# PERIPHERAL.net
KiCad netlist of a schematic drawn in Altium Designer
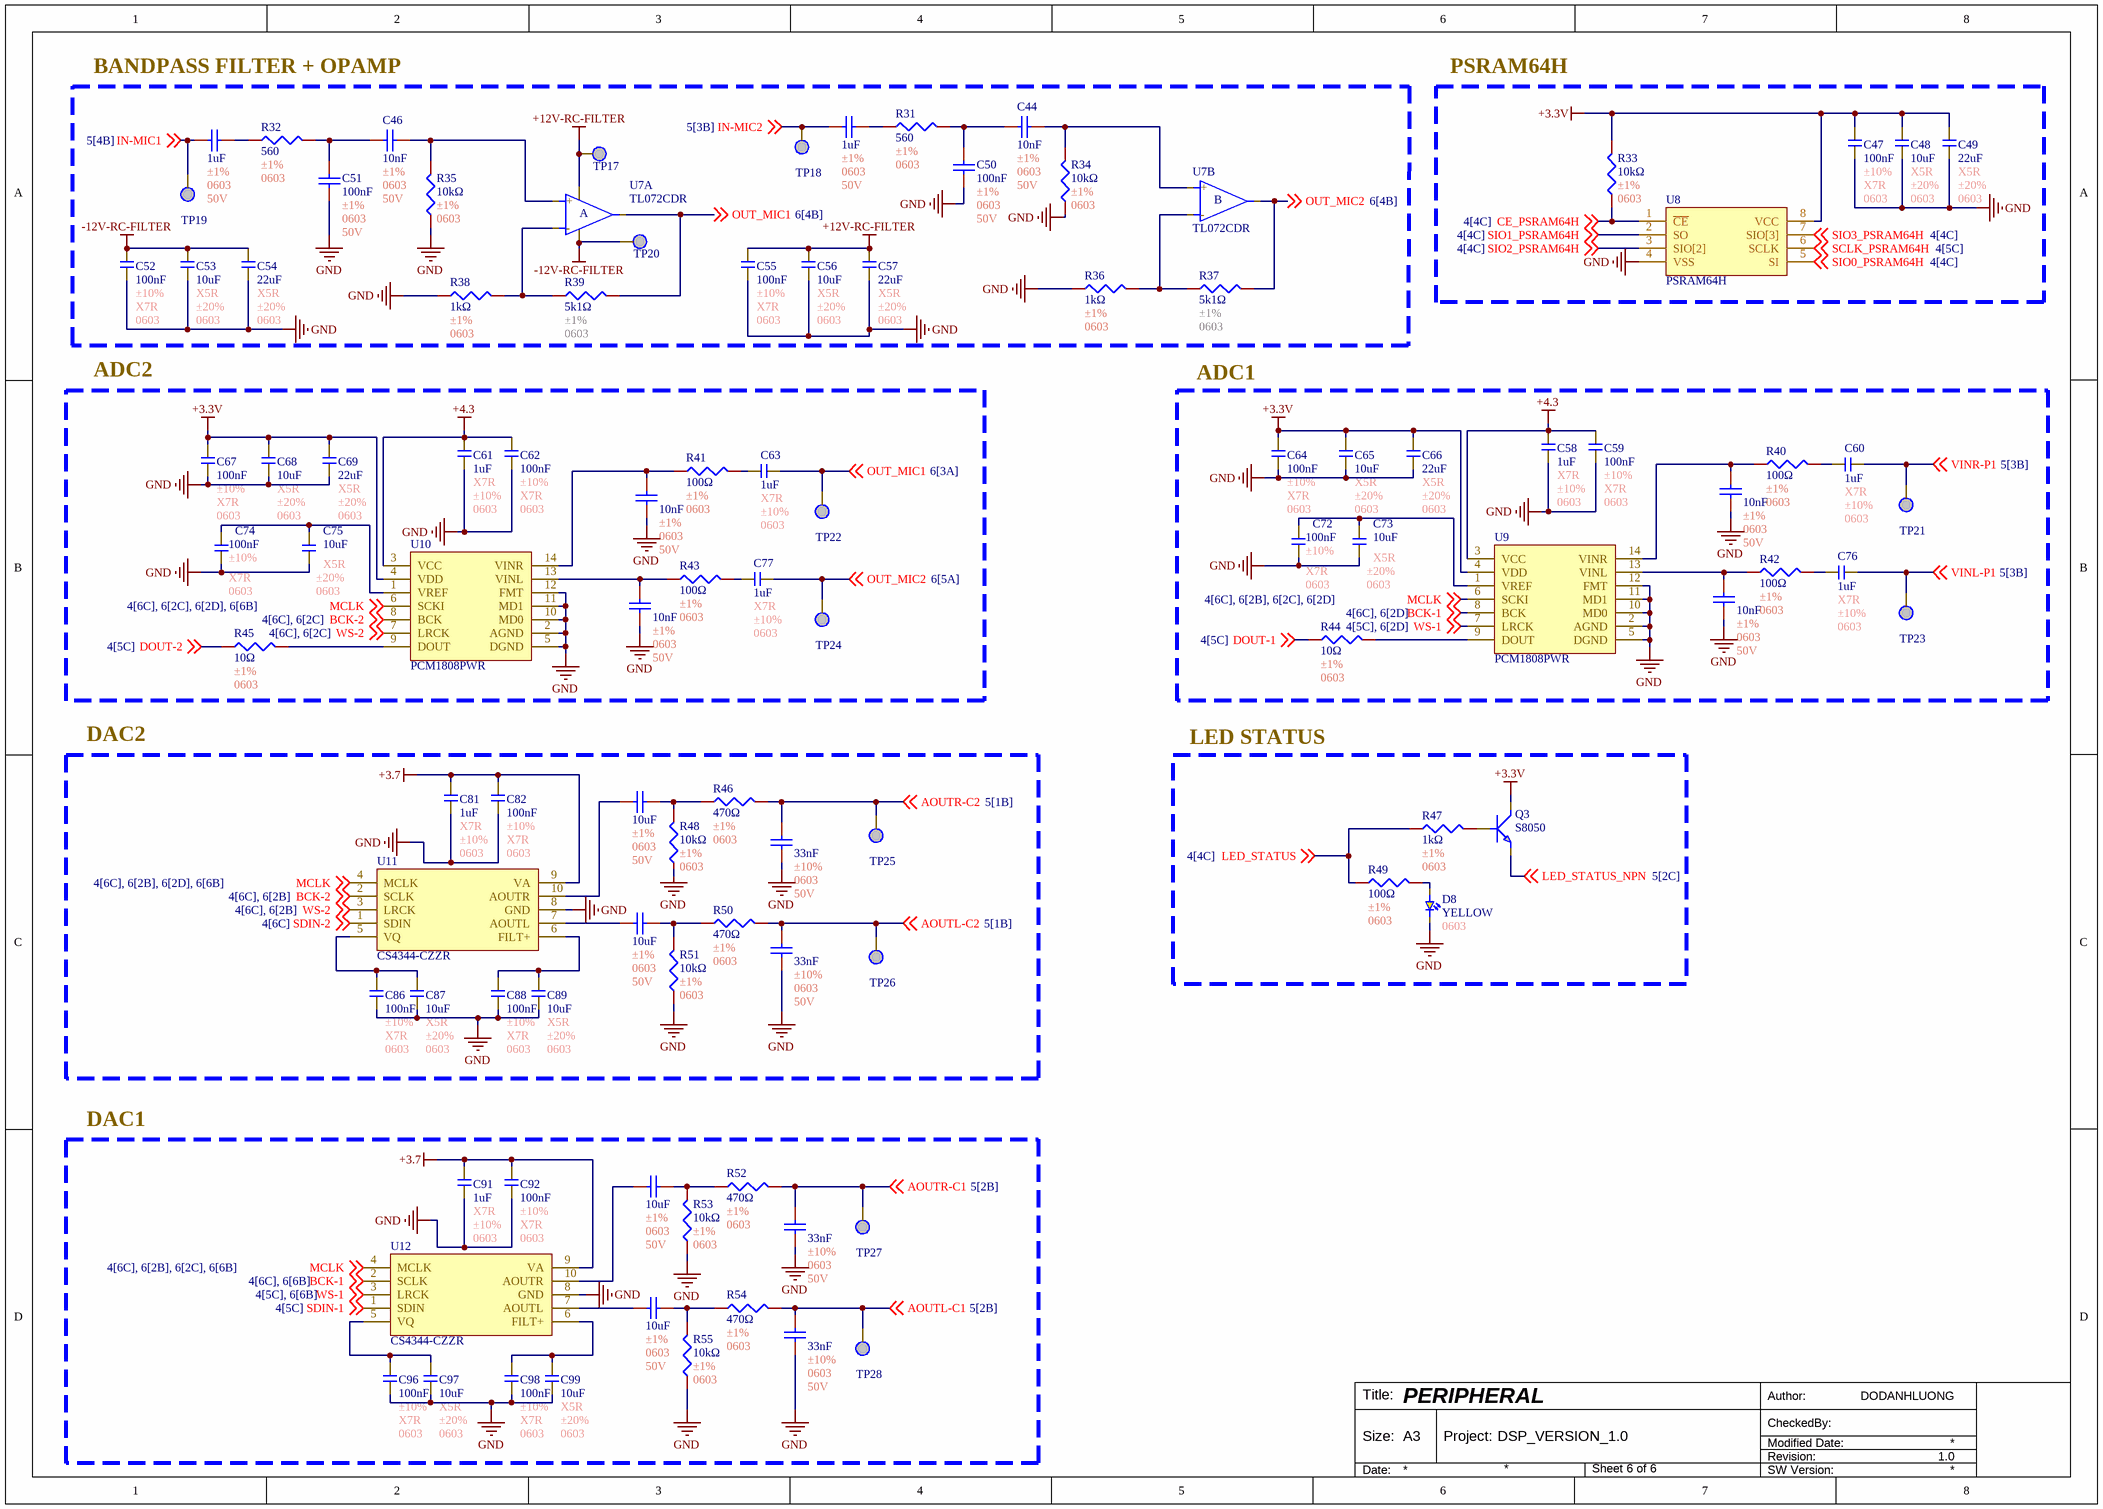
[diagram p0: PERIPHERAL.SchDoc]

(export (version "E")
  (design (tool "Eeschema 10.0.6"))
  (components
    (comp (ref "C43")
      (value "1uF")
      (footprint "C0603")
      (description "50V 10pF NP0 ±1% 0402 Multilayer Ceramic Capacitors MLCC - SMD/SMT ROHS")
      (fields
        (field (name "MANUFACTURER") "YAGEO")
        (field (name "MFR. PART #") "CC0402FRNPO9BN100")
        (field (name "TOLERANCE") "±1%")
        (field (name "PACKAGE") "0603")
        (field (name "VOLTAGE RATING") "50V")
      )
      (libsource (lib "Capital") (part "C0603_1uF_±1%"))
    )
    (comp (ref "C44")
      (value "10nF")
      (footprint "C0603")
      (description "50V 10pF NP0 ±1% 0402 Multilayer Ceramic Capacitors MLCC - SMD/SMT ROHS")
      (fields
        (field (name "MANUFACTURER") "YAGEO")
        (field (name "MFR. PART #") "CC0402FRNPO9BN100")
        (field (name "TOLERANCE") "±1%")
        (field (name "PACKAGE") "0603")
        (field (name "VOLTAGE RATING") "50V")
      )
      (libsource (lib "Capital") (part "C0603_10nF_±1%"))
    )
    (comp (ref "C45")
      (value "1uF")
      (footprint "C0603")
      (description "50V 10pF NP0 ±1% 0402 Multilayer Ceramic Capacitors MLCC - SMD/SMT ROHS")
      (fields
        (field (name "MANUFACTURER") "YAGEO")
        (field (name "MFR. PART #") "CC0402FRNPO9BN100")
        (field (name "TOLERANCE") "±1%")
        (field (name "PACKAGE") "0603")
        (field (name "VOLTAGE RATING") "50V")
      )
      (libsource (lib "Capital") (part "C0603_1uF_±1%"))
    )
    (comp (ref "C46")
      (value "10nF")
      (footprint "C0603")
      (description "50V 10pF NP0 ±1% 0402 Multilayer Ceramic Capacitors MLCC - SMD/SMT ROHS")
      (fields
        (field (name "MANUFACTURER") "YAGEO")
        (field (name "MFR. PART #") "CC0402FRNPO9BN100")
        (field (name "TOLERANCE") "±1%")
        (field (name "PACKAGE") "0603")
        (field (name "VOLTAGE RATING") "50V")
      )
      (libsource (lib "Capital") (part "C0603_10nF_±1%"))
    )
    (comp (ref "C47")
      (value "100nF")
      (footprint "C0603")
      (description "50V 100nF X7R ±10% 0603 Multilayer Ceramic Capacitors MLCC - SMD/SMT ROHS")
      (fields
        (field (name "MANUFACTURER") "YAGEO")
        (field (name "MFR. PART #") "CC0603KRX7R9BB104")
        (field (name "TOLERANCE") "±10%")
        (field (name "TEMPERATURE COEFFICIENT") "X7R")
        (field (name "PACKAGE") "0603")
      )
      (libsource (lib "DSP_VERSION_1.0") (part "C0603_100nF_±10%_X7R"))
    )
    (comp (ref "C48")
      (value "10uF")
      (footprint "C0603")
      (description "25V 10uF X5R ±20% 0603 Multilayer Ceramic Capacitors MLCC - SMD/SMT ROHS")
      (fields
        (field (name "MANUFACTURER") "YAGEO")
        (field (name "MFR. PART #") "CC0603MRX5R8BB106")
        (field (name "TEMPERATURE COEFFICIENT") "X5R")
        (field (name "TOLERANCE") "±20%")
        (field (name "PACKAGE") "0603")
      )
      (libsource (lib "DSP_VERSION_1.0") (part "C0603_10uF_±10%_X7R"))
    )
    (comp (ref "C49")
      (value "22uF")
      (footprint "C0603")
      (description "6.3V 22uF X5R ±20% 0603 Multilayer Ceramic Capacitors MLCC - SMD/SMT ROHS")
      (fields
        (field (name "MANUFACTURER") "YAGEO")
        (field (name "MFR. PART #") "CC0603MRX5R5BB226")
        (field (name "TEMPERATURE COEFFICIENT") "X5R")
        (field (name "TOLERANCE") "±20%")
        (field (name "PACKAGE") "0603")
      )
      (libsource (lib "DSP_VERSION_1.0") (part "C0603_22uF_±20%_X5R"))
    )
    (comp (ref "C50")
      (value "100nF")
      (footprint "C0603")
      (description "50V 10pF NP0 ±1% 0402 Multilayer Ceramic Capacitors MLCC - SMD/SMT ROHS")
      (fields
        (field (name "MANUFACTURER") "YAGEO")
        (field (name "MFR. PART #") "CC0402FRNPO9BN100")
        (field (name "TOLERANCE") "±1%")
        (field (name "PACKAGE") "0603")
        (field (name "VOLTAGE RATING") "50V")
      )
      (libsource (lib "Capital") (part "C0603_10nF_±1%"))
    )
    (comp (ref "C51")
      (value "100nF")
      (footprint "C0603")
      (description "50V 10pF NP0 ±1% 0402 Multilayer Ceramic Capacitors MLCC - SMD/SMT ROHS")
      (fields
        (field (name "MANUFACTURER") "YAGEO")
        (field (name "MFR. PART #") "CC0402FRNPO9BN100")
        (field (name "TOLERANCE") "±1%")
        (field (name "PACKAGE") "0603")
        (field (name "VOLTAGE RATING") "50V")
      )
      (libsource (lib "Capital") (part "C0603_10nF_±1%"))
    )
    (comp (ref "C52")
      (value "100nF")
      (footprint "C0603")
      (description "50V 100nF X7R ±10% 0603 Multilayer Ceramic Capacitors MLCC - SMD/SMT ROHS")
      (fields
        (field (name "MANUFACTURER") "YAGEO")
        (field (name "MFR. PART #") "CC0603KRX7R9BB104")
        (field (name "TOLERANCE") "±10%")
        (field (name "TEMPERATURE COEFFICIENT") "X7R")
        (field (name "PACKAGE") "0603")
      )
      (libsource (lib "DSP_VERSION_1.0") (part "C0603_100nF_±10%_X7R"))
    )
    (comp (ref "C53")
      (value "10uF")
      (footprint "C0603")
      (description "25V 10uF X5R ±20% 0603 Multilayer Ceramic Capacitors MLCC - SMD/SMT ROHS")
      (fields
        (field (name "MANUFACTURER") "YAGEO")
        (field (name "MFR. PART #") "CC0603MRX5R8BB106")
        (field (name "TEMPERATURE COEFFICIENT") "X5R")
        (field (name "TOLERANCE") "±20%")
        (field (name "PACKAGE") "0603")
      )
      (libsource (lib "DSP_VERSION_1.0") (part "C0603_10uF_±10%_X7R"))
    )
    (comp (ref "C54")
      (value "22uF")
      (footprint "C0603")
      (description "6.3V 22uF X5R ±20% 0603 Multilayer Ceramic Capacitors MLCC - SMD/SMT ROHS")
      (fields
        (field (name "MANUFACTURER") "YAGEO")
        (field (name "MFR. PART #") "CC0603MRX5R5BB226")
        (field (name "TEMPERATURE COEFFICIENT") "X5R")
        (field (name "TOLERANCE") "±20%")
        (field (name "PACKAGE") "0603")
      )
      (libsource (lib "DSP_VERSION_1.0") (part "C0603_22uF_±20%_X5R"))
    )
    (comp (ref "C55")
      (value "100nF")
      (footprint "C0603")
      (description "50V 100nF X7R ±10% 0603 Multilayer Ceramic Capacitors MLCC - SMD/SMT ROHS")
      (fields
        (field (name "MANUFACTURER") "YAGEO")
        (field (name "MFR. PART #") "CC0603KRX7R9BB104")
        (field (name "TOLERANCE") "±10%")
        (field (name "TEMPERATURE COEFFICIENT") "X7R")
        (field (name "PACKAGE") "0603")
      )
      (libsource (lib "DSP_VERSION_1.0") (part "C0603_100nF_±10%_X7R"))
    )
    (comp (ref "C56")
      (value "10uF")
      (footprint "C0603")
      (description "25V 10uF X5R ±20% 0603 Multilayer Ceramic Capacitors MLCC - SMD/SMT ROHS")
      (fields
        (field (name "MANUFACTURER") "YAGEO")
        (field (name "MFR. PART #") "CC0603MRX5R8BB106")
        (field (name "TEMPERATURE COEFFICIENT") "X5R")
        (field (name "TOLERANCE") "±20%")
        (field (name "PACKAGE") "0603")
      )
      (libsource (lib "DSP_VERSION_1.0") (part "C0603_10uF_±10%_X7R"))
    )
    (comp (ref "C57")
      (value "22uF")
      (footprint "C0603")
      (description "6.3V 22uF X5R ±20% 0603 Multilayer Ceramic Capacitors MLCC - SMD/SMT ROHS")
      (fields
        (field (name "MANUFACTURER") "YAGEO")
        (field (name "MFR. PART #") "CC0603MRX5R5BB226")
        (field (name "TEMPERATURE COEFFICIENT") "X5R")
        (field (name "TOLERANCE") "±20%")
        (field (name "PACKAGE") "0603")
      )
      (libsource (lib "DSP_VERSION_1.0") (part "C0603_22uF_±20%_X5R"))
    )
    (comp (ref "C58")
      (value "1uF")
      (footprint "C0603")
      (description "50V 1uF X7R ±10% 0603 Multilayer Ceramic Capacitors MLCC - SMD/SMT ROHS")
      (fields
        (field (name "MANUFACTURER") "YAGEO")
        (field (name "MFR. PART #") "CC0603KRX7R9BB105")
        (field (name "TEMPERATURE COEFFICIENT") "X7R")
        (field (name "TOLERANCE") "±10%")
        (field (name "PACKAGE") "0603")
      )
      (libsource (lib "DSP_VERSION_1.0") (part "C0603_1uF_±10%_X7R"))
    )
    (comp (ref "C59")
      (value "100nF")
      (footprint "C0603")
      (description "50V 100nF X7R ±10% 0603 Multilayer Ceramic Capacitors MLCC - SMD/SMT ROHS")
      (fields
        (field (name "MANUFACTURER") "YAGEO")
        (field (name "MFR. PART #") "CC0603KRX7R9BB104")
        (field (name "TOLERANCE") "±10%")
        (field (name "TEMPERATURE COEFFICIENT") "X7R")
        (field (name "PACKAGE") "0603")
      )
      (libsource (lib "DSP_VERSION_1.0") (part "C0603_100nF_±10%_X7R"))
    )
    (comp (ref "C60")
      (value "1uF")
      (footprint "C0603")
      (description "50V 1uF X7R ±10% 0603 Multilayer Ceramic Capacitors MLCC - SMD/SMT ROHS")
      (fields
        (field (name "MANUFACTURER") "YAGEO")
        (field (name "MFR. PART #") "CC0603KRX7R9BB105")
        (field (name "TEMPERATURE COEFFICIENT") "X7R")
        (field (name "TOLERANCE") "±10%")
        (field (name "PACKAGE") "0603")
      )
      (libsource (lib "DSP_VERSION_1.0") (part "C0603_1uF_±10%_X7R"))
    )
    (comp (ref "C61")
      (value "1uF")
      (footprint "C0603")
      (description "50V 1uF X7R ±10% 0603 Multilayer Ceramic Capacitors MLCC - SMD/SMT ROHS")
      (fields
        (field (name "MANUFACTURER") "YAGEO")
        (field (name "MFR. PART #") "CC0603KRX7R9BB105")
        (field (name "TEMPERATURE COEFFICIENT") "X7R")
        (field (name "TOLERANCE") "±10%")
        (field (name "PACKAGE") "0603")
      )
      (libsource (lib "DSP_VERSION_1.0") (part "C0603_1uF_±10%_X7R"))
    )
    (comp (ref "C62")
      (value "100nF")
      (footprint "C0603")
      (description "50V 100nF X7R ±10% 0603 Multilayer Ceramic Capacitors MLCC - SMD/SMT ROHS")
      (fields
        (field (name "MANUFACTURER") "YAGEO")
        (field (name "MFR. PART #") "CC0603KRX7R9BB104")
        (field (name "TOLERANCE") "±10%")
        (field (name "TEMPERATURE COEFFICIENT") "X7R")
        (field (name "PACKAGE") "0603")
      )
      (libsource (lib "DSP_VERSION_1.0") (part "C0603_100nF_±10%_X7R"))
    )
    (comp (ref "C63")
      (value "1uF")
      (footprint "C0603")
      (description "50V 1uF X7R ±10% 0603 Multilayer Ceramic Capacitors MLCC - SMD/SMT ROHS")
      (fields
        (field (name "MANUFACTURER") "YAGEO")
        (field (name "MFR. PART #") "CC0603KRX7R9BB105")
        (field (name "TEMPERATURE COEFFICIENT") "X7R")
        (field (name "TOLERANCE") "±10%")
        (field (name "PACKAGE") "0603")
      )
      (libsource (lib "DSP_VERSION_1.0") (part "C0603_1uF_±10%_X7R"))
    )
    (comp (ref "C64")
      (value "100nF")
      (footprint "C0603")
      (description "50V 100nF X7R ±10% 0603 Multilayer Ceramic Capacitors MLCC - SMD/SMT ROHS")
      (fields
        (field (name "MANUFACTURER") "YAGEO")
        (field (name "MFR. PART #") "CC0603KRX7R9BB104")
        (field (name "TOLERANCE") "±10%")
        (field (name "TEMPERATURE COEFFICIENT") "X7R")
        (field (name "PACKAGE") "0603")
      )
      (libsource (lib "DSP_VERSION_1.0") (part "C0603_100nF_±10%_X7R"))
    )
    (comp (ref "C65")
      (value "10uF")
      (footprint "C0603")
      (description "25V 10uF X5R ±20% 0603 Multilayer Ceramic Capacitors MLCC - SMD/SMT ROHS")
      (fields
        (field (name "MANUFACTURER") "YAGEO")
        (field (name "MFR. PART #") "CC0603MRX5R8BB106")
        (field (name "TEMPERATURE COEFFICIENT") "X5R")
        (field (name "TOLERANCE") "±20%")
        (field (name "PACKAGE") "0603")
      )
      (libsource (lib "DSP_VERSION_1.0") (part "C0603_10uF_±10%_X7R"))
    )
    (comp (ref "C66")
      (value "22uF")
      (footprint "C0603")
      (description "6.3V 22uF X5R ±20% 0603 Multilayer Ceramic Capacitors MLCC - SMD/SMT ROHS")
      (fields
        (field (name "MANUFACTURER") "YAGEO")
        (field (name "MFR. PART #") "CC0603MRX5R5BB226")
        (field (name "TEMPERATURE COEFFICIENT") "X5R")
        (field (name "TOLERANCE") "±20%")
        (field (name "PACKAGE") "0603")
      )
      (libsource (lib "DSP_VERSION_1.0") (part "C0603_22uF_±20%_X5R"))
    )
    (comp (ref "C67")
      (value "100nF")
      (footprint "C0603")
      (description "50V 100nF X7R ±10% 0603 Multilayer Ceramic Capacitors MLCC - SMD/SMT ROHS")
      (fields
        (field (name "MANUFACTURER") "YAGEO")
        (field (name "MFR. PART #") "CC0603KRX7R9BB104")
        (field (name "TOLERANCE") "±10%")
        (field (name "TEMPERATURE COEFFICIENT") "X7R")
        (field (name "PACKAGE") "0603")
      )
      (libsource (lib "DSP_VERSION_1.0") (part "C0603_100nF_±10%_X7R"))
    )
    (comp (ref "C68")
      (value "10uF")
      (footprint "C0603")
      (description "25V 10uF X5R ±20% 0603 Multilayer Ceramic Capacitors MLCC - SMD/SMT ROHS")
      (fields
        (field (name "MANUFACTURER") "YAGEO")
        (field (name "MFR. PART #") "CC0603MRX5R8BB106")
        (field (name "TEMPERATURE COEFFICIENT") "X5R")
        (field (name "TOLERANCE") "±20%")
        (field (name "PACKAGE") "0603")
      )
      (libsource (lib "DSP_VERSION_1.0") (part "C0603_10uF_±10%_X7R"))
    )
    (comp (ref "C69")
      (value "22uF")
      (footprint "C0603")
      (description "6.3V 22uF X5R ±20% 0603 Multilayer Ceramic Capacitors MLCC - SMD/SMT ROHS")
      (fields
        (field (name "MANUFACTURER") "YAGEO")
        (field (name "MFR. PART #") "CC0603MRX5R5BB226")
        (field (name "TEMPERATURE COEFFICIENT") "X5R")
        (field (name "TOLERANCE") "±20%")
        (field (name "PACKAGE") "0603")
      )
      (libsource (lib "DSP_VERSION_1.0") (part "C0603_22uF_±20%_X5R"))
    )
    (comp (ref "C70")
      (value "10nF")
      (footprint "C0603")
      (description "50V 10pF NP0 ±1% 0402 Multilayer Ceramic Capacitors MLCC - SMD/SMT ROHS")
      (fields
        (field (name "MANUFACTURER") "YAGEO")
        (field (name "MFR. PART #") "CC0402FRNPO9BN100")
        (field (name "TOLERANCE") "±1%")
        (field (name "PACKAGE") "0603")
        (field (name "VOLTAGE RATING") "50V")
      )
      (libsource (lib "Capital") (part "C0603_10nF_±1%"))
    )
    (comp (ref "C71")
      (value "10nF")
      (footprint "C0603")
      (description "50V 10pF NP0 ±1% 0402 Multilayer Ceramic Capacitors MLCC - SMD/SMT ROHS")
      (fields
        (field (name "MANUFACTURER") "YAGEO")
        (field (name "MFR. PART #") "CC0402FRNPO9BN100")
        (field (name "TOLERANCE") "±1%")
        (field (name "PACKAGE") "0603")
        (field (name "VOLTAGE RATING") "50V")
      )
      (libsource (lib "Capital") (part "C0603_10nF_±1%"))
    )
    (comp (ref "C72")
      (value "100nF")
      (footprint "C0603")
      (description "50V 100nF X7R ±10% 0603 Multilayer Ceramic Capacitors MLCC - SMD/SMT ROHS")
      (fields
        (field (name "MANUFACTURER") "YAGEO")
        (field (name "MFR. PART #") "CC0603KRX7R9BB104")
        (field (name "TOLERANCE") "±10%")
        (field (name "TEMPERATURE COEFFICIENT") "X7R")
        (field (name "PACKAGE") "0603")
      )
      (libsource (lib "DSP_VERSION_1.0") (part "C0603_100nF_±10%_X7R"))
    )
    (comp (ref "C73")
      (value "10uF")
      (footprint "C0603")
      (description "25V 10uF X5R ±20% 0603 Multilayer Ceramic Capacitors MLCC - SMD/SMT ROHS")
      (fields
        (field (name "MANUFACTURER") "YAGEO")
        (field (name "MFR. PART #") "CC0603MRX5R8BB106")
        (field (name "TEMPERATURE COEFFICIENT") "X5R")
        (field (name "TOLERANCE") "±20%")
        (field (name "PACKAGE") "0603")
      )
      (libsource (lib "DSP_VERSION_1.0") (part "C0603_10uF_±10%_X7R"))
    )
    (comp (ref "C74")
      (value "100nF")
      (footprint "C0603")
      (description "50V 100nF X7R ±10% 0603 Multilayer Ceramic Capacitors MLCC - SMD/SMT ROHS")
      (fields
        (field (name "MANUFACTURER") "YAGEO")
        (field (name "MFR. PART #") "CC0603KRX7R9BB104")
        (field (name "TOLERANCE") "±10%")
        (field (name "TEMPERATURE COEFFICIENT") "X7R")
        (field (name "PACKAGE") "0603")
      )
      (libsource (lib "DSP_VERSION_1.0") (part "C0603_100nF_±10%_X7R"))
    )
    (comp (ref "C75")
      (value "10uF")
      (footprint "C0603")
      (description "25V 10uF X5R ±20% 0603 Multilayer Ceramic Capacitors MLCC - SMD/SMT ROHS")
      (fields
        (field (name "MANUFACTURER") "YAGEO")
        (field (name "MFR. PART #") "CC0603MRX5R8BB106")
        (field (name "TEMPERATURE COEFFICIENT") "X5R")
        (field (name "TOLERANCE") "±20%")
        (field (name "PACKAGE") "0603")
      )
      (libsource (lib "DSP_VERSION_1.0") (part "C0603_10uF_±10%_X7R"))
    )
    (comp (ref "C76")
      (value "1uF")
      (footprint "C0603")
      (description "50V 1uF X7R ±10% 0603 Multilayer Ceramic Capacitors MLCC - SMD/SMT ROHS")
      (fields
        (field (name "MANUFACTURER") "YAGEO")
        (field (name "MFR. PART #") "CC0603KRX7R9BB105")
        (field (name "TEMPERATURE COEFFICIENT") "X7R")
        (field (name "TOLERANCE") "±10%")
        (field (name "PACKAGE") "0603")
      )
      (libsource (lib "DSP_VERSION_1.0") (part "C0603_1uF_±10%_X7R"))
    )
    (comp (ref "C77")
      (value "1uF")
      (footprint "C0603")
      (description "50V 1uF X7R ±10% 0603 Multilayer Ceramic Capacitors MLCC - SMD/SMT ROHS")
      (fields
        (field (name "MANUFACTURER") "YAGEO")
        (field (name "MFR. PART #") "CC0603KRX7R9BB105")
        (field (name "TEMPERATURE COEFFICIENT") "X7R")
        (field (name "TOLERANCE") "±10%")
        (field (name "PACKAGE") "0603")
      )
      (libsource (lib "DSP_VERSION_1.0") (part "C0603_1uF_±10%_X7R"))
    )
    (comp (ref "C78")
      (value "10nF")
      (footprint "C0603")
      (description "50V 10pF NP0 ±1% 0402 Multilayer Ceramic Capacitors MLCC - SMD/SMT ROHS")
      (fields
        (field (name "MANUFACTURER") "YAGEO")
        (field (name "MFR. PART #") "CC0402FRNPO9BN100")
        (field (name "TOLERANCE") "±1%")
        (field (name "PACKAGE") "0603")
        (field (name "VOLTAGE RATING") "50V")
      )
      (libsource (lib "Capital") (part "C0603_10nF_±1%"))
    )
    (comp (ref "C79")
      (value "10nF")
      (footprint "C0603")
      (description "50V 10pF NP0 ±1% 0402 Multilayer Ceramic Capacitors MLCC - SMD/SMT ROHS")
      (fields
        (field (name "MANUFACTURER") "YAGEO")
        (field (name "MFR. PART #") "CC0402FRNPO9BN100")
        (field (name "TOLERANCE") "±1%")
        (field (name "PACKAGE") "0603")
        (field (name "VOLTAGE RATING") "50V")
      )
      (libsource (lib "Capital") (part "C0603_10nF_±1%"))
    )
    (comp (ref "C80")
      (value "10uF")
      (footprint "C0603")
      (description "50V 10pF NP0 ±1% 0402 Multilayer Ceramic Capacitors MLCC - SMD/SMT ROHS")
      (fields
        (field (name "MANUFACTURER") "YAGEO")
        (field (name "MFR. PART #") "CC0402FRNPO9BN100")
        (field (name "TOLERANCE") "±1%")
        (field (name "PACKAGE") "0603")
        (field (name "VOLTAGE RATING") "50V")
      )
      (libsource (lib "Capital") (part "C0603_10uF_±1%"))
    )
    (comp (ref "C81")
      (value "1uF")
      (footprint "C0603")
      (description "50V 1uF X7R ±10% 0603 Multilayer Ceramic Capacitors MLCC - SMD/SMT ROHS")
      (fields
        (field (name "MANUFACTURER") "YAGEO")
        (field (name "MFR. PART #") "CC0603KRX7R9BB105")
        (field (name "TEMPERATURE COEFFICIENT") "X7R")
        (field (name "TOLERANCE") "±10%")
        (field (name "PACKAGE") "0603")
      )
      (libsource (lib "DSP_VERSION_1.0") (part "C0603_1uF_±10%_X7R"))
    )
    (comp (ref "C82")
      (value "100nF")
      (footprint "C0603")
      (description "50V 100nF X7R ±10% 0603 Multilayer Ceramic Capacitors MLCC - SMD/SMT ROHS")
      (fields
        (field (name "MANUFACTURER") "YAGEO")
        (field (name "MFR. PART #") "CC0603KRX7R9BB104")
        (field (name "TOLERANCE") "±10%")
        (field (name "TEMPERATURE COEFFICIENT") "X7R")
        (field (name "PACKAGE") "0603")
      )
      (libsource (lib "DSP_VERSION_1.0") (part "C0603_100nF_±10%_X7R"))
    )
    (comp (ref "C83")
      (value "33nF")
      (footprint "C0603")
      (description "100mW Thick Film Resistor 75V ±100ppm/℃ ±1% 470Ω 0603 Chip Resistor - Surface Mount ROHS")
      (fields
        (field (name "MANUFACTURER") "YAGEO")
        (field (name "MFR. PART #") "CC0603KRX7R9BB333")
        (field (name "TOLERANCE") "±10%")
        (field (name "PACKAGE") "0603")
        (field (name "VOLTAGE RATING") "50V")
      )
      (libsource (lib "Capital") (part "C0603_33nF_±10%"))
    )
    (comp (ref "C84")
      (value "10uF")
      (footprint "C0603")
      (description "50V 10pF NP0 ±1% 0402 Multilayer Ceramic Capacitors MLCC - SMD/SMT ROHS")
      (fields
        (field (name "MANUFACTURER") "YAGEO")
        (field (name "MFR. PART #") "CC0402FRNPO9BN100")
        (field (name "TOLERANCE") "±1%")
        (field (name "PACKAGE") "0603")
        (field (name "VOLTAGE RATING") "50V")
      )
      (libsource (lib "Capital") (part "C0603_10uF_±1%"))
    )
    (comp (ref "C85")
      (value "33nF")
      (footprint "C0603")
      (description "100mW Thick Film Resistor 75V ±100ppm/℃ ±1% 470Ω 0603 Chip Resistor - Surface Mount ROHS")
      (fields
        (field (name "MANUFACTURER") "YAGEO")
        (field (name "MFR. PART #") "CC0603KRX7R9BB333")
        (field (name "TOLERANCE") "±10%")
        (field (name "PACKAGE") "0603")
        (field (name "VOLTAGE RATING") "50V")
      )
      (libsource (lib "Capital") (part "C0603_33nF_±10%"))
    )
    (comp (ref "C86")
      (value "100nF")
      (footprint "C0603")
      (description "50V 100nF X7R ±10% 0603 Multilayer Ceramic Capacitors MLCC - SMD/SMT ROHS")
      (fields
        (field (name "MANUFACTURER") "YAGEO")
        (field (name "MFR. PART #") "CC0603KRX7R9BB104")
        (field (name "TOLERANCE") "±10%")
        (field (name "TEMPERATURE COEFFICIENT") "X7R")
        (field (name "PACKAGE") "0603")
      )
      (libsource (lib "DSP_VERSION_1.0") (part "C0603_100nF_±10%_X7R"))
    )
    (comp (ref "C87")
      (value "10uF")
      (footprint "C0603")
      (description "25V 10uF X5R ±20% 0603 Multilayer Ceramic Capacitors MLCC - SMD/SMT ROHS")
      (fields
        (field (name "MANUFACTURER") "YAGEO")
        (field (name "MFR. PART #") "CC0603MRX5R8BB106")
        (field (name "TEMPERATURE COEFFICIENT") "X5R")
        (field (name "TOLERANCE") "±20%")
        (field (name "PACKAGE") "0603")
      )
      (libsource (lib "DSP_VERSION_1.0") (part "C0603_10uF_±10%_X7R"))
    )
    (comp (ref "C88")
      (value "100nF")
      (footprint "C0603")
      (description "50V 100nF X7R ±10% 0603 Multilayer Ceramic Capacitors MLCC - SMD/SMT ROHS")
      (fields
        (field (name "MANUFACTURER") "YAGEO")
        (field (name "MFR. PART #") "CC0603KRX7R9BB104")
        (field (name "TOLERANCE") "±10%")
        (field (name "TEMPERATURE COEFFICIENT") "X7R")
        (field (name "PACKAGE") "0603")
      )
      (libsource (lib "DSP_VERSION_1.0") (part "C0603_100nF_±10%_X7R"))
    )
    (comp (ref "C89")
      (value "10uF")
      (footprint "C0603")
      (description "25V 10uF X5R ±20% 0603 Multilayer Ceramic Capacitors MLCC - SMD/SMT ROHS")
      (fields
        (field (name "MANUFACTURER") "YAGEO")
        (field (name "MFR. PART #") "CC0603MRX5R8BB106")
        (field (name "TEMPERATURE COEFFICIENT") "X5R")
        (field (name "TOLERANCE") "±20%")
        (field (name "PACKAGE") "0603")
      )
      (libsource (lib "DSP_VERSION_1.0") (part "C0603_10uF_±10%_X7R"))
    )
    (comp (ref "C90")
      (value "10uF")
      (footprint "C0603")
      (description "50V 10pF NP0 ±1% 0402 Multilayer Ceramic Capacitors MLCC - SMD/SMT ROHS")
      (fields
        (field (name "MANUFACTURER") "YAGEO")
        (field (name "MFR. PART #") "CC0402FRNPO9BN100")
        (field (name "TOLERANCE") "±1%")
        (field (name "PACKAGE") "0603")
        (field (name "VOLTAGE RATING") "50V")
      )
      (libsource (lib "Capital") (part "C0603_10uF_±1%"))
    )
    (comp (ref "C91")
      (value "1uF")
      (footprint "C0603")
      (description "50V 1uF X7R ±10% 0603 Multilayer Ceramic Capacitors MLCC - SMD/SMT ROHS")
      (fields
        (field (name "MANUFACTURER") "YAGEO")
        (field (name "MFR. PART #") "CC0603KRX7R9BB105")
        (field (name "TEMPERATURE COEFFICIENT") "X7R")
        (field (name "TOLERANCE") "±10%")
        (field (name "PACKAGE") "0603")
      )
      (libsource (lib "DSP_VERSION_1.0") (part "C0603_1uF_±10%_X7R"))
    )
    (comp (ref "C92")
      (value "100nF")
      (footprint "C0603")
      (description "50V 100nF X7R ±10% 0603 Multilayer Ceramic Capacitors MLCC - SMD/SMT ROHS")
      (fields
        (field (name "MANUFACTURER") "YAGEO")
        (field (name "MFR. PART #") "CC0603KRX7R9BB104")
        (field (name "TOLERANCE") "±10%")
        (field (name "TEMPERATURE COEFFICIENT") "X7R")
        (field (name "PACKAGE") "0603")
      )
      (libsource (lib "DSP_VERSION_1.0") (part "C0603_100nF_±10%_X7R"))
    )
    (comp (ref "C93")
      (value "33nF")
      (footprint "C0603")
      (description "100mW Thick Film Resistor 75V ±100ppm/℃ ±1% 470Ω 0603 Chip Resistor - Surface Mount ROHS")
      (fields
        (field (name "MANUFACTURER") "YAGEO")
        (field (name "MFR. PART #") "CC0603KRX7R9BB333")
        (field (name "TOLERANCE") "±10%")
        (field (name "PACKAGE") "0603")
        (field (name "VOLTAGE RATING") "50V")
      )
      (libsource (lib "Capital") (part "C0603_33nF_±10%"))
    )
    (comp (ref "C94")
      (value "10uF")
      (footprint "C0603")
      (description "50V 10pF NP0 ±1% 0402 Multilayer Ceramic Capacitors MLCC - SMD/SMT ROHS")
      (fields
        (field (name "MANUFACTURER") "YAGEO")
        (field (name "MFR. PART #") "CC0402FRNPO9BN100")
        (field (name "TOLERANCE") "±1%")
        (field (name "PACKAGE") "0603")
        (field (name "VOLTAGE RATING") "50V")
      )
      (libsource (lib "Capital") (part "C0603_10uF_±1%"))
    )
    (comp (ref "C95")
      (value "33nF")
      (footprint "C0603")
      (description "100mW Thick Film Resistor 75V ±100ppm/℃ ±1% 470Ω 0603 Chip Resistor - Surface Mount ROHS")
      (fields
        (field (name "MANUFACTURER") "YAGEO")
        (field (name "MFR. PART #") "CC0603KRX7R9BB333")
        (field (name "TOLERANCE") "±10%")
        (field (name "PACKAGE") "0603")
        (field (name "VOLTAGE RATING") "50V")
      )
      (libsource (lib "Capital") (part "C0603_33nF_±10%"))
    )
    (comp (ref "C96")
      (value "100nF")
      (footprint "C0603")
      (description "50V 100nF X7R ±10% 0603 Multilayer Ceramic Capacitors MLCC - SMD/SMT ROHS")
      (fields
        (field (name "MANUFACTURER") "YAGEO")
        (field (name "MFR. PART #") "CC0603KRX7R9BB104")
        (field (name "TOLERANCE") "±10%")
        (field (name "TEMPERATURE COEFFICIENT") "X7R")
        (field (name "PACKAGE") "0603")
      )
      (libsource (lib "DSP_VERSION_1.0") (part "C0603_100nF_±10%_X7R"))
    )
    (comp (ref "C97")
      (value "10uF")
      (footprint "C0603")
      (description "25V 10uF X5R ±20% 0603 Multilayer Ceramic Capacitors MLCC - SMD/SMT ROHS")
      (fields
        (field (name "MANUFACTURER") "YAGEO")
        (field (name "MFR. PART #") "CC0603MRX5R8BB106")
        (field (name "TEMPERATURE COEFFICIENT") "X5R")
        (field (name "TOLERANCE") "±20%")
        (field (name "PACKAGE") "0603")
      )
      (libsource (lib "DSP_VERSION_1.0") (part "C0603_10uF_±10%_X7R"))
    )
    (comp (ref "C98")
      (value "100nF")
      (footprint "C0603")
      (description "50V 100nF X7R ±10% 0603 Multilayer Ceramic Capacitors MLCC - SMD/SMT ROHS")
      (fields
        (field (name "MANUFACTURER") "YAGEO")
        (field (name "MFR. PART #") "CC0603KRX7R9BB104")
        (field (name "TOLERANCE") "±10%")
        (field (name "TEMPERATURE COEFFICIENT") "X7R")
        (field (name "PACKAGE") "0603")
      )
      (libsource (lib "DSP_VERSION_1.0") (part "C0603_100nF_±10%_X7R"))
    )
    (comp (ref "C99")
      (value "10uF")
      (footprint "C0603")
      (description "25V 10uF X5R ±20% 0603 Multilayer Ceramic Capacitors MLCC - SMD/SMT ROHS")
      (fields
        (field (name "MANUFACTURER") "YAGEO")
        (field (name "MFR. PART #") "CC0603MRX5R8BB106")
        (field (name "TEMPERATURE COEFFICIENT") "X5R")
        (field (name "TOLERANCE") "±20%")
        (field (name "PACKAGE") "0603")
      )
      (libsource (lib "DSP_VERSION_1.0") (part "C0603_10uF_±10%_X7R"))
    )
    (comp (ref "D8")
      (value "YELLOW")
      (footprint "LED0603")
      (description "25mcd~40mcd Water Clear -40℃~+85℃ 624nm Red 120° 60mW 0402 LED Indication - Discrete ROHS")
      (fields
        (field (name "MANUFACTURER") "XINGLIGHT")
        (field (name "MFR. PART #") "XL-1005UGC")
        (field (name "PACKAGE") "0603")
      )
      (libsource (lib "LED") (part "D0603_YELLOW"))
    )
    (comp (ref "Q3")
      (value "S8050")
      (footprint "S8050")
      (description "25V 300mW 500mA SOT-23 Bipolar (BJT) ROHS")
      (fields (field (name "MANUFACTURER") "JSMSEMI") (field (name "LCSC PART #") "C916390"))
      (libsource (lib "Transistor") (part "S8050"))
    )
    (comp (ref "R31")
      (value "560")
      (footprint "R0603")
      (description "62.5mW Thick Film Resistor 50V ±1% ±200ppm/℃ 10Ω 0402 Chip Resistor - Surface Mount ROHS")
      (fields
        (field (name "MANUFACTURER") "YAGEO")
        (field (name "MFR. PART #") "RC0402FR-0710RL")
        (field (name "TOLERANCE") "±1%")
        (field (name "PACKAGE") "0603")
      )
      (libsource (lib "Resistor") (part "R0603_1kΩ_±1%"))
    )
    (comp (ref "R32")
      (value "560")
      (footprint "R0603")
      (description "62.5mW Thick Film Resistor 50V ±1% ±200ppm/℃ 10Ω 0402 Chip Resistor - Surface Mount ROHS")
      (fields
        (field (name "MANUFACTURER") "YAGEO")
        (field (name "MFR. PART #") "RC0402FR-0710RL")
        (field (name "TOLERANCE") "±1%")
        (field (name "PACKAGE") "0603")
      )
      (libsource (lib "Resistor") (part "R0603_1kΩ_±1%"))
    )
    (comp (ref "R33")
      (value "10kΩ")
      (footprint "R0603")
      (description "62.5mW Thick Film Resistor 50V ±1% ±200ppm/℃ 10Ω 0402 Chip Resistor - Surface Mount ROHS")
      (fields
        (field (name "MANUFACTURER") "YAGEO")
        (field (name "MFR. PART #") "RC0402FR-0710RL")
        (field (name "TOLERANCE") "±1%")
        (field (name "PACKAGE") "0603")
      )
      (libsource (lib "Resistor") (part "R0603_10kΩ_±1%"))
    )
    (comp (ref "R34")
      (value "10kΩ")
      (footprint "R0603")
      (description "62.5mW Thick Film Resistor 50V ±1% ±200ppm/℃ 10Ω 0402 Chip Resistor - Surface Mount ROHS")
      (fields
        (field (name "MANUFACTURER") "YAGEO")
        (field (name "MFR. PART #") "RC0402FR-0710RL")
        (field (name "TOLERANCE") "±1%")
        (field (name "PACKAGE") "0603")
      )
      (libsource (lib "Resistor") (part "R0603_10kΩ_±1%"))
    )
    (comp (ref "R35")
      (value "10kΩ")
      (footprint "R0603")
      (description "62.5mW Thick Film Resistor 50V ±1% ±200ppm/℃ 10Ω 0402 Chip Resistor - Surface Mount ROHS")
      (fields
        (field (name "MANUFACTURER") "YAGEO")
        (field (name "MFR. PART #") "RC0402FR-0710RL")
        (field (name "TOLERANCE") "±1%")
        (field (name "PACKAGE") "0603")
      )
      (libsource (lib "Resistor") (part "R0603_10kΩ_±1%"))
    )
    (comp (ref "R36")
      (value "1kΩ")
      (footprint "R0603")
      (description "62.5mW Thick Film Resistor 50V ±1% ±200ppm/℃ 10Ω 0402 Chip Resistor - Surface Mount ROHS")
      (fields
        (field (name "MANUFACTURER") "YAGEO")
        (field (name "MFR. PART #") "RC0402FR-0710RL")
        (field (name "TOLERANCE") "±1%")
        (field (name "PACKAGE") "0603")
      )
      (libsource (lib "Resistor") (part "R0603_1kΩ_±1%"))
    )
    (comp (ref "R37")
      (value "5k1Ω")
      (footprint "R0603")
      (description "100mW Thick Film Resistor 75V ±100ppm/℃ ±1% 5.1kΩ 0603 Chip Resistor - Surface Mount ROHS")
      (fields
        (field (name "MANUFACTURER") "FOJAN")
        (field (name "MFR. PART #") "FRC0603F5101TS")
        (field (name "TOLERANCE") "±1%")
        (field (name "PACKAGE") "0603")
      )
      (libsource (lib "Resistor") (part "R0603_5k1Ω_±1%"))
    )
    (comp (ref "R38")
      (value "1kΩ")
      (footprint "R0603")
      (description "62.5mW Thick Film Resistor 50V ±1% ±200ppm/℃ 10Ω 0402 Chip Resistor - Surface Mount ROHS")
      (fields
        (field (name "MANUFACTURER") "YAGEO")
        (field (name "MFR. PART #") "RC0402FR-0710RL")
        (field (name "TOLERANCE") "±1%")
        (field (name "PACKAGE") "0603")
      )
      (libsource (lib "Resistor") (part "R0603_1kΩ_±1%"))
    )
    (comp (ref "R39")
      (value "5k1Ω")
      (footprint "R0603")
      (description "100mW Thick Film Resistor 75V ±100ppm/℃ ±1% 5.1kΩ 0603 Chip Resistor - Surface Mount ROHS")
      (fields
        (field (name "MANUFACTURER") "FOJAN")
        (field (name "MFR. PART #") "FRC0603F5101TS")
        (field (name "TOLERANCE") "±1%")
        (field (name "PACKAGE") "0603")
      )
      (libsource (lib "Resistor") (part "R0603_5k1Ω_±1%"))
    )
    (comp (ref "R40")
      (value "100Ω")
      (footprint "R0603")
      (description "62.5mW Thick Film Resistor 50V ±1% ±200ppm/℃ 10Ω 0402 Chip Resistor - Surface Mount ROHS")
      (fields
        (field (name "MANUFACTURER") "YAGEO")
        (field (name "MFR. PART #") "RC0402FR-0710RL")
        (field (name "TOLERANCE") "±1%")
        (field (name "PACKAGE") "0603")
      )
      (libsource (lib "Resistor") (part "R0603_100Ω_±1%"))
    )
    (comp (ref "R41")
      (value "100Ω")
      (footprint "R0603")
      (description "62.5mW Thick Film Resistor 50V ±1% ±200ppm/℃ 10Ω 0402 Chip Resistor - Surface Mount ROHS")
      (fields
        (field (name "MANUFACTURER") "YAGEO")
        (field (name "MFR. PART #") "RC0402FR-0710RL")
        (field (name "TOLERANCE") "±1%")
        (field (name "PACKAGE") "0603")
      )
      (libsource (lib "Resistor") (part "R0603_100Ω_±1%"))
    )
    (comp (ref "R42")
      (value "100Ω")
      (footprint "R0603")
      (description "62.5mW Thick Film Resistor 50V ±1% ±200ppm/℃ 10Ω 0402 Chip Resistor - Surface Mount ROHS")
      (fields
        (field (name "MANUFACTURER") "YAGEO")
        (field (name "MFR. PART #") "RC0402FR-0710RL")
        (field (name "TOLERANCE") "±1%")
        (field (name "PACKAGE") "0603")
      )
      (libsource (lib "Resistor") (part "R0603_100Ω_±1%"))
    )
    (comp (ref "R43")
      (value "100Ω")
      (footprint "R0603")
      (description "62.5mW Thick Film Resistor 50V ±1% ±200ppm/℃ 10Ω 0402 Chip Resistor - Surface Mount ROHS")
      (fields
        (field (name "MANUFACTURER") "YAGEO")
        (field (name "MFR. PART #") "RC0402FR-0710RL")
        (field (name "TOLERANCE") "±1%")
        (field (name "PACKAGE") "0603")
      )
      (libsource (lib "Resistor") (part "R0603_100Ω_±1%"))
    )
    (comp (ref "R44")
      (value "10Ω")
      (footprint "R0603")
      (description "62.5mW Thick Film Resistor 50V ±1% ±200ppm/℃ 10Ω 0402 Chip Resistor - Surface Mount ROHS")
      (fields
        (field (name "MANUFACTURER") "YAGEO")
        (field (name "MFR. PART #") "RC0402FR-0710RL")
        (field (name "TOLERANCE") "±1%")
        (field (name "PACKAGE") "0603")
      )
      (libsource (lib "Resistor") (part "R0603_10Ω_±1%"))
    )
    (comp (ref "R45")
      (value "10Ω")
      (footprint "R0603")
      (description "62.5mW Thick Film Resistor 50V ±1% ±200ppm/℃ 10Ω 0402 Chip Resistor - Surface Mount ROHS")
      (fields
        (field (name "MANUFACTURER") "YAGEO")
        (field (name "MFR. PART #") "RC0402FR-0710RL")
        (field (name "TOLERANCE") "±1%")
        (field (name "PACKAGE") "0603")
      )
      (libsource (lib "Resistor") (part "R0603_10Ω_±1%"))
    )
    (comp (ref "R46")
      (value "470Ω")
      (footprint "R0603")
      (description "62.5mW Thick Film Resistor 50V ±1% ±200ppm/℃ 10Ω 0402 Chip Resistor - Surface Mount ROHS")
      (fields
        (field (name "MANUFACTURER") "YAGEO")
        (field (name "MFR. PART #") "RC0603FR-07470RL")
        (field (name "TOLERANCE") "±1%")
        (field (name "PACKAGE") "0603")
      )
      (libsource (lib "Resistor") (part "R0603_470Ω_±1%_1"))
    )
    (comp (ref "R47")
      (value "1kΩ")
      (footprint "R0603")
      (description "62.5mW Thick Film Resistor 50V ±1% ±200ppm/℃ 10Ω 0402 Chip Resistor - Surface Mount ROHS")
      (fields
        (field (name "MANUFACTURER") "YAGEO")
        (field (name "MFR. PART #") "RC0402FR-0710RL")
        (field (name "TOLERANCE") "±1%")
        (field (name "PACKAGE") "0603")
      )
      (libsource (lib "Resistor") (part "R0603_1kΩ_±1%"))
    )
    (comp (ref "R48")
      (value "10kΩ")
      (footprint "R0603")
      (description "62.5mW Thick Film Resistor 50V ±1% ±200ppm/℃ 10Ω 0402 Chip Resistor - Surface Mount ROHS")
      (fields
        (field (name "MANUFACTURER") "YAGEO")
        (field (name "MFR. PART #") "RC0402FR-0710RL")
        (field (name "TOLERANCE") "±1%")
        (field (name "PACKAGE") "0603")
      )
      (libsource (lib "Resistor") (part "R0603_10kΩ_±1%"))
    )
    (comp (ref "R49")
      (value "100Ω")
      (footprint "R0603")
      (description "62.5mW Thick Film Resistor 50V ±1% ±200ppm/℃ 10Ω 0402 Chip Resistor - Surface Mount ROHS")
      (fields
        (field (name "MANUFACTURER") "YAGEO")
        (field (name "MFR. PART #") "RC0402FR-0710RL")
        (field (name "TOLERANCE") "±1%")
        (field (name "PACKAGE") "0603")
      )
      (libsource (lib "Resistor") (part "R0603_100Ω_±1%"))
    )
    (comp (ref "R50")
      (value "470Ω")
      (footprint "R0603")
      (description "62.5mW Thick Film Resistor 50V ±1% ±200ppm/℃ 10Ω 0402 Chip Resistor - Surface Mount ROHS")
      (fields
        (field (name "MANUFACTURER") "YAGEO")
        (field (name "MFR. PART #") "RC0603FR-07470RL")
        (field (name "TOLERANCE") "±1%")
        (field (name "PACKAGE") "0603")
      )
      (libsource (lib "Resistor") (part "R0603_470Ω_±1%_1"))
    )
    (comp (ref "R51")
      (value "10kΩ")
      (footprint "R0603")
      (description "62.5mW Thick Film Resistor 50V ±1% ±200ppm/℃ 10Ω 0402 Chip Resistor - Surface Mount ROHS")
      (fields
        (field (name "MANUFACTURER") "YAGEO")
        (field (name "MFR. PART #") "RC0402FR-0710RL")
        (field (name "TOLERANCE") "±1%")
        (field (name "PACKAGE") "0603")
      )
      (libsource (lib "Resistor") (part "R0603_10kΩ_±1%"))
    )
    (comp (ref "R52")
      (value "470Ω")
      (footprint "R0603")
      (description "62.5mW Thick Film Resistor 50V ±1% ±200ppm/℃ 10Ω 0402 Chip Resistor - Surface Mount ROHS")
      (fields
        (field (name "MANUFACTURER") "YAGEO")
        (field (name "MFR. PART #") "RC0603FR-07470RL")
        (field (name "TOLERANCE") "±1%")
        (field (name "PACKAGE") "0603")
      )
      (libsource (lib "Resistor") (part "R0603_470Ω_±1%_1"))
    )
    (comp (ref "R53")
      (value "10kΩ")
      (footprint "R0603")
      (description "62.5mW Thick Film Resistor 50V ±1% ±200ppm/℃ 10Ω 0402 Chip Resistor - Surface Mount ROHS")
      (fields
        (field (name "MANUFACTURER") "YAGEO")
        (field (name "MFR. PART #") "RC0402FR-0710RL")
        (field (name "TOLERANCE") "±1%")
        (field (name "PACKAGE") "0603")
      )
      (libsource (lib "Resistor") (part "R0603_10kΩ_±1%"))
    )
    (comp (ref "R54")
      (value "470Ω")
      (footprint "R0603")
      (description "62.5mW Thick Film Resistor 50V ±1% ±200ppm/℃ 10Ω 0402 Chip Resistor - Surface Mount ROHS")
      (fields
        (field (name "MANUFACTURER") "YAGEO")
        (field (name "MFR. PART #") "RC0603FR-07470RL")
        (field (name "TOLERANCE") "±1%")
        (field (name "PACKAGE") "0603")
      )
      (libsource (lib "Resistor") (part "R0603_470Ω_±1%_1"))
    )
    (comp (ref "R55")
      (value "10kΩ")
      (footprint "R0603")
      (description "62.5mW Thick Film Resistor 50V ±1% ±200ppm/℃ 10Ω 0402 Chip Resistor - Surface Mount ROHS")
      (fields
        (field (name "MANUFACTURER") "YAGEO")
        (field (name "MFR. PART #") "RC0402FR-0710RL")
        (field (name "TOLERANCE") "±1%")
        (field (name "PACKAGE") "0603")
      )
      (libsource (lib "Resistor") (part "R0603_10kΩ_±1%"))
    )
    (comp (ref "TP17") (value "TP") (footprint "TP") (libsource (lib "Other") (part "TP")))
    (comp (ref "TP18") (value "TP") (footprint "TP") (libsource (lib "Other") (part "TP")))
    (comp (ref "TP19") (value "TP") (footprint "TP") (libsource (lib "Other") (part "TP")))
    (comp (ref "TP20") (value "TP") (footprint "TP") (libsource (lib "Other") (part "TP")))
    (comp (ref "TP21") (value "TP") (footprint "TP") (libsource (lib "Other") (part "TP")))
    (comp (ref "TP22") (value "TP") (footprint "TP") (libsource (lib "Other") (part "TP")))
    (comp (ref "TP23") (value "TP") (footprint "TP") (libsource (lib "Other") (part "TP")))
    (comp (ref "TP24") (value "TP") (footprint "TP") (libsource (lib "Other") (part "TP")))
    (comp (ref "TP25") (value "TP") (footprint "TP") (libsource (lib "Other") (part "TP")))
    (comp (ref "TP26") (value "TP") (footprint "TP") (libsource (lib "Other") (part "TP")))
    (comp (ref "TP27") (value "TP") (footprint "TP") (libsource (lib "Other") (part "TP")))
    (comp (ref "TP28") (value "TP") (footprint "TP") (libsource (lib "Other") (part "TP")))
    (comp (ref "U7")
      (value "TL072CDR")
      (footprint "TL072CDR")
      (description "3mV 65pA 3MHz 13V/us 2 SOIC-8 FET Input Amplifiers ROHS")
      (fields (field (name "MANUFACTURER") "TI") (field (name "LCSC PART #") "C67473"))
      (libsource (lib "IC") (part "TL072CDR"))
    )
    (comp (ref "U8") (value "PSRAM64H") (footprint "PSRAM64H") (libsource (lib "IC") (part "PSRAM64H")))
    (comp (ref "U9")
      (value "PCM1808PWR")
      (footprint "PCM1808PWR")
      (description "4.5V~5.5V 24 I2S TSSOP-14 ADCs/DACs - Special Purpose ROHS")
      (fields (field (name "MANUFACTURER") "TI") (field (name "LCSC PART #") "C55513"))
      (libsource (lib "IC") (part "PCM1808PWR"))
    )
    (comp (ref "U10")
      (value "PCM1808PWR")
      (footprint "PCM1808PWR")
      (description "4.5V~5.5V 24 I2S TSSOP-14 ADCs/DACs - Special Purpose ROHS")
      (fields (field (name "MANUFACTURER") "TI") (field (name "LCSC PART #") "C55513"))
      (libsource (lib "IC") (part "PCM1808PWR"))
    )
    (comp (ref "U11")
      (value "CS4344-CZZR")
      (footprint "CS4344-CZZR")
      (description "250ms I2S 3.3V~5V 24 TSSOP-10-3mm Digital to Analog Converters (DAC) ROHS")
      (fields (field (name "MANUFACTURER") "Cirrus Logic") (field (name "LCSC PART #") "C8952"))
      (libsource (lib "IC") (part "CS4344-CZZR"))
    )
    (comp (ref "U12")
      (value "CS4344-CZZR")
      (footprint "CS4344-CZZR")
      (description "250ms I2S 3.3V~5V 24 TSSOP-10-3mm Digital to Analog Converters (DAC) ROHS")
      (fields (field (name "MANUFACTURER") "Cirrus Logic") (field (name "LCSC PART #") "C8952"))
      (libsource (lib "IC") (part "CS4344-CZZR"))
    )
  )
  (nets
    (net (code "1") (name "+3.3V") (class "Default")
      (node (ref "C47") (pin "2") (pinfunction "2_2") (pintype "passive"))
      (node (ref "C48") (pin "2") (pinfunction "2_2") (pintype "passive"))
      (node (ref "C49") (pin "2") (pinfunction "2_2") (pintype "passive"))
      (node (ref "C64") (pin "2") (pinfunction "2_2") (pintype "passive"))
      (node (ref "C65") (pin "2") (pinfunction "2_2") (pintype "passive"))
      (node (ref "C66") (pin "2") (pinfunction "2_2") (pintype "passive"))
      (node (ref "C67") (pin "2") (pinfunction "2_2") (pintype "passive"))
      (node (ref "C68") (pin "2") (pinfunction "2_2") (pintype "passive"))
      (node (ref "C69") (pin "2") (pinfunction "2_2") (pintype "passive"))
      (node (ref "Q3") (pin "3") (pinfunction "C_3") (pintype "passive"))
      (node (ref "R33") (pin "2") (pinfunction "2_2") (pintype "passive"))
      (node (ref "U10") (pin "4") (pinfunction "VDD_4") (pintype "passive"))
      (node (ref "U8") (pin "8") (pinfunction "VCC_8") (pintype "passive"))
      (node (ref "U9") (pin "4") (pinfunction "VDD_4") (pintype "passive"))
    )
    (net (code "2") (name "+3.7") (class "Default")
      (node (ref "C81") (pin "2") (pinfunction "2_2") (pintype "passive"))
      (node (ref "C82") (pin "2") (pinfunction "2_2") (pintype "passive"))
      (node (ref "C91") (pin "2") (pinfunction "2_2") (pintype "passive"))
      (node (ref "C92") (pin "2") (pinfunction "2_2") (pintype "passive"))
      (node (ref "U11") (pin "9") (pinfunction "VA_9") (pintype "passive"))
      (node (ref "U12") (pin "9") (pinfunction "VA_9") (pintype "passive"))
    )
    (net (code "3") (name "+4.3") (class "Default")
      (node (ref "C58") (pin "2") (pinfunction "2_2") (pintype "passive"))
      (node (ref "C59") (pin "2") (pinfunction "2_2") (pintype "passive"))
      (node (ref "C61") (pin "2") (pinfunction "2_2") (pintype "passive"))
      (node (ref "C62") (pin "2") (pinfunction "2_2") (pintype "passive"))
      (node (ref "U10") (pin "3") (pinfunction "VCC_3") (pintype "passive"))
      (node (ref "U9") (pin "3") (pinfunction "VCC_3") (pintype "passive"))
    )
    (net (code "4") (name "+12V-RC-FILTER") (class "Default")
      (node (ref "C55") (pin "2") (pinfunction "2_2") (pintype "passive"))
      (node (ref "C56") (pin "2") (pinfunction "2_2") (pintype "passive"))
      (node (ref "C57") (pin "2") (pinfunction "2_2") (pintype "passive"))
      (node (ref "TP17") (pin "1") (pinfunction "1_1") (pintype "passive"))
      (node (ref "U7") (pin "8") (pinfunction "8_8") (pintype "passive"))
    )
    (net (code "5") (name "-12V-RC-FILTER") (class "Default")
      (node (ref "C52") (pin "2") (pinfunction "2_2") (pintype "passive"))
      (node (ref "C53") (pin "2") (pinfunction "2_2") (pintype "passive"))
      (node (ref "C54") (pin "2") (pinfunction "2_2") (pintype "passive"))
      (node (ref "TP20") (pin "1") (pinfunction "1_1") (pintype "passive"))
      (node (ref "U7") (pin "4") (pinfunction "GND_4") (pintype "passive"))
    )
    (net (code "6") (name "AOUTL-C1") (class "Default")
      (node (ref "C95") (pin "1") (pinfunction "1_1") (pintype "passive"))
      (node (ref "R54") (pin "2") (pinfunction "2_2") (pintype "passive"))
      (node (ref "TP28") (pin "1") (pinfunction "1_1") (pintype "passive"))
    )
    (net (code "7") (name "AOUTL-C2") (class "Default")
      (node (ref "C85") (pin "1") (pinfunction "1_1") (pintype "passive"))
      (node (ref "R50") (pin "2") (pinfunction "2_2") (pintype "passive"))
      (node (ref "TP26") (pin "1") (pinfunction "1_1") (pintype "passive"))
    )
    (net (code "8") (name "AOUTR-C1") (class "Default")
      (node (ref "C93") (pin "1") (pinfunction "1_1") (pintype "passive"))
      (node (ref "R52") (pin "2") (pinfunction "2_2") (pintype "passive"))
      (node (ref "TP27") (pin "1") (pinfunction "1_1") (pintype "passive"))
    )
    (net (code "9") (name "AOUTR-C2") (class "Default")
      (node (ref "C83") (pin "1") (pinfunction "1_1") (pintype "passive"))
      (node (ref "R46") (pin "2") (pinfunction "2_2") (pintype "passive"))
      (node (ref "TP25") (pin "1") (pinfunction "1_1") (pintype "passive"))
    )
    (net (code "10") (name "BCK-1") (class "Default")
      (node (ref "U12") (pin "2") (pinfunction "SCLK_2") (pintype "passive"))
      (node (ref "U9") (pin "8") (pinfunction "BCK_8") (pintype "passive"))
    )
    (net (code "11") (name "BCK-2") (class "Default")
      (node (ref "U10") (pin "8") (pinfunction "BCK_8") (pintype "passive"))
      (node (ref "U11") (pin "2") (pinfunction "SCLK_2") (pintype "passive"))
    )
    (net (code "12") (name "CE_PSRAM64H") (class "Default")
      (node (ref "R33") (pin "1") (pinfunction "1_1") (pintype "passive"))
      (node (ref "U8") (pin "1") (pinfunction "~{CE}_1") (pintype "passive"))
    )
    (net (code "13") (name "DOUT-1") (class "Default")
      (node (ref "R44") (pin "1") (pinfunction "1_1") (pintype "passive"))
    )
    (net (code "14") (name "DOUT-2") (class "Default")
      (node (ref "R45") (pin "1") (pinfunction "1_1") (pintype "passive"))
    )
    (net (code "15") (name "GND") (class "Default")
      (node (ref "C47") (pin "1") (pinfunction "1_1") (pintype "passive"))
      (node (ref "C48") (pin "1") (pinfunction "1_1") (pintype "passive"))
      (node (ref "C49") (pin "1") (pinfunction "1_1") (pintype "passive"))
      (node (ref "C50") (pin "2") (pinfunction "2_2") (pintype "passive"))
      (node (ref "C51") (pin "2") (pinfunction "2_2") (pintype "passive"))
      (node (ref "C52") (pin "1") (pinfunction "1_1") (pintype "passive"))
      (node (ref "C53") (pin "1") (pinfunction "1_1") (pintype "passive"))
      (node (ref "C54") (pin "1") (pinfunction "1_1") (pintype "passive"))
      (node (ref "C55") (pin "1") (pinfunction "1_1") (pintype "passive"))
      (node (ref "C56") (pin "1") (pinfunction "1_1") (pintype "passive"))
      (node (ref "C57") (pin "1") (pinfunction "1_1") (pintype "passive"))
      (node (ref "C58") (pin "1") (pinfunction "1_1") (pintype "passive"))
      (node (ref "C59") (pin "1") (pinfunction "1_1") (pintype "passive"))
      (node (ref "C61") (pin "1") (pinfunction "1_1") (pintype "passive"))
      (node (ref "C62") (pin "1") (pinfunction "1_1") (pintype "passive"))
      (node (ref "C64") (pin "1") (pinfunction "1_1") (pintype "passive"))
      (node (ref "C65") (pin "1") (pinfunction "1_1") (pintype "passive"))
      (node (ref "C66") (pin "1") (pinfunction "1_1") (pintype "passive"))
      (node (ref "C67") (pin "1") (pinfunction "1_1") (pintype "passive"))
      (node (ref "C68") (pin "1") (pinfunction "1_1") (pintype "passive"))
      (node (ref "C69") (pin "1") (pinfunction "1_1") (pintype "passive"))
      (node (ref "C70") (pin "2") (pinfunction "2_2") (pintype "passive"))
      (node (ref "C71") (pin "2") (pinfunction "2_2") (pintype "passive"))
      (node (ref "C72") (pin "1") (pinfunction "1_1") (pintype "passive"))
      (node (ref "C73") (pin "1") (pinfunction "1_1") (pintype "passive"))
      (node (ref "C74") (pin "1") (pinfunction "1_1") (pintype "passive"))
      (node (ref "C75") (pin "1") (pinfunction "1_1") (pintype "passive"))
      (node (ref "C78") (pin "2") (pinfunction "2_2") (pintype "passive"))
      (node (ref "C79") (pin "2") (pinfunction "2_2") (pintype "passive"))
      (node (ref "C81") (pin "1") (pinfunction "1_1") (pintype "passive"))
      (node (ref "C82") (pin "1") (pinfunction "1_1") (pintype "passive"))
      (node (ref "C83") (pin "2") (pinfunction "2_2") (pintype "passive"))
      (node (ref "C85") (pin "2") (pinfunction "2_2") (pintype "passive"))
      (node (ref "C86") (pin "1") (pinfunction "1_1") (pintype "passive"))
      (node (ref "C87") (pin "1") (pinfunction "1_1") (pintype "passive"))
      (node (ref "C88") (pin "1") (pinfunction "1_1") (pintype "passive"))
      (node (ref "C89") (pin "1") (pinfunction "1_1") (pintype "passive"))
      (node (ref "C91") (pin "1") (pinfunction "1_1") (pintype "passive"))
      (node (ref "C92") (pin "1") (pinfunction "1_1") (pintype "passive"))
      (node (ref "C93") (pin "2") (pinfunction "2_2") (pintype "passive"))
      (node (ref "C95") (pin "2") (pinfunction "2_2") (pintype "passive"))
      (node (ref "C96") (pin "1") (pinfunction "1_1") (pintype "passive"))
      (node (ref "C97") (pin "1") (pinfunction "1_1") (pintype "passive"))
      (node (ref "C98") (pin "1") (pinfunction "1_1") (pintype "passive"))
      (node (ref "C99") (pin "1") (pinfunction "1_1") (pintype "passive"))
      (node (ref "D8") (pin "1") (pinfunction "1_1") (pintype "passive"))
      (node (ref "R34") (pin "1") (pinfunction "1_1") (pintype "passive"))
      (node (ref "R35") (pin "1") (pinfunction "1_1") (pintype "passive"))
      (node (ref "R36") (pin "1") (pinfunction "1_1") (pintype "passive"))
      (node (ref "R38") (pin "1") (pinfunction "1_1") (pintype "passive"))
      (node (ref "R48") (pin "1") (pinfunction "1_1") (pintype "passive"))
      (node (ref "R51") (pin "1") (pinfunction "1_1") (pintype "passive"))
      (node (ref "R53") (pin "1") (pinfunction "1_1") (pintype "passive"))
      (node (ref "R55") (pin "1") (pinfunction "1_1") (pintype "passive"))
      (node (ref "U10") (pin "10") (pinfunction "MD0_10") (pintype "passive"))
      (node (ref "U10") (pin "11") (pinfunction "MD1_11") (pintype "passive"))
      (node (ref "U10") (pin "12") (pinfunction "FMT_12") (pintype "passive"))
      (node (ref "U10") (pin "2") (pinfunction "AGND_2") (pintype "passive"))
      (node (ref "U10") (pin "5") (pinfunction "DGND_5") (pintype "passive"))
      (node (ref "U11") (pin "8") (pinfunction "GND_8") (pintype "passive"))
      (node (ref "U12") (pin "8") (pinfunction "GND_8") (pintype "passive"))
      (node (ref "U8") (pin "4") (pinfunction "VSS_4") (pintype "passive"))
      (node (ref "U9") (pin "10") (pinfunction "MD0_10") (pintype "passive"))
      (node (ref "U9") (pin "11") (pinfunction "MD1_11") (pintype "passive"))
      (node (ref "U9") (pin "12") (pinfunction "FMT_12") (pintype "passive"))
      (node (ref "U9") (pin "2") (pinfunction "AGND_2") (pintype "passive"))
      (node (ref "U9") (pin "5") (pinfunction "DGND_5") (pintype "passive"))
    )
    (net (code "16") (name "IN-MIC1") (class "Default")
      (node (ref "C45") (pin "2") (pinfunction "2_2") (pintype "passive"))
      (node (ref "TP19") (pin "1") (pinfunction "1_1") (pintype "passive"))
    )
    (net (code "17") (name "IN-MIC2") (class "Default")
      (node (ref "C43") (pin "2") (pinfunction "2_2") (pintype "passive"))
      (node (ref "TP18") (pin "1") (pinfunction "1_1") (pintype "passive"))
    )
    (net (code "18") (name "LED_STATUS") (class "Default")
      (node (ref "R47") (pin "1") (pinfunction "1_1") (pintype "passive"))
      (node (ref "R49") (pin "1") (pinfunction "1_1") (pintype "passive"))
    )
    (net (code "19") (name "LED_STATUS_NPN") (class "Default")
      (node (ref "Q3") (pin "2") (pinfunction "E_2") (pintype "passive"))
    )
    (net (code "20") (name "MCLK") (class "Default")
      (node (ref "U10") (pin "6") (pinfunction "SCKI_6") (pintype "passive"))
      (node (ref "U11") (pin "4") (pinfunction "MCLK_4") (pintype "passive"))
      (node (ref "U12") (pin "4") (pinfunction "MCLK_4") (pintype "passive"))
      (node (ref "U9") (pin "6") (pinfunction "SCKI_6") (pintype "passive"))
    )
    (net (code "21") (name "Net-(C43-Pad1)") (class "Default")
      (node (ref "C43") (pin "1") (pinfunction "1_1") (pintype "passive"))
      (node (ref "R31") (pin "1") (pinfunction "1_1") (pintype "passive"))
    )
    (net (code "22") (name "Net-(C44-Pad1)") (class "Default")
      (node (ref "C44") (pin "1") (pinfunction "1_1") (pintype "passive"))
      (node (ref "C50") (pin "1") (pinfunction "1_1") (pintype "passive"))
      (node (ref "R31") (pin "2") (pinfunction "2_2") (pintype "passive"))
    )
    (net (code "23") (name "Net-(C45-Pad1)") (class "Default")
      (node (ref "C45") (pin "1") (pinfunction "1_1") (pintype "passive"))
      (node (ref "R32") (pin "1") (pinfunction "1_1") (pintype "passive"))
    )
    (net (code "24") (name "Net-(C46-Pad1)") (class "Default")
      (node (ref "C46") (pin "1") (pinfunction "1_1") (pintype "passive"))
      (node (ref "C51") (pin "1") (pinfunction "1_1") (pintype "passive"))
      (node (ref "R32") (pin "2") (pinfunction "2_2") (pintype "passive"))
    )
    (net (code "25") (name "Net-(C60-Pad2)") (class "Default")
      (node (ref "C60") (pin "2") (pinfunction "2_2") (pintype "passive"))
      (node (ref "R40") (pin "2") (pinfunction "2_2") (pintype "passive"))
    )
    (net (code "26") (name "Net-(C63-Pad2)") (class "Default")
      (node (ref "C63") (pin "2") (pinfunction "2_2") (pintype "passive"))
      (node (ref "R41") (pin "2") (pinfunction "2_2") (pintype "passive"))
    )
    (net (code "27") (name "Net-(C76-Pad2)") (class "Default")
      (node (ref "C76") (pin "2") (pinfunction "2_2") (pintype "passive"))
      (node (ref "R42") (pin "2") (pinfunction "2_2") (pintype "passive"))
    )
    (net (code "28") (name "Net-(C77-Pad2)") (class "Default")
      (node (ref "C77") (pin "2") (pinfunction "2_2") (pintype "passive"))
      (node (ref "R43") (pin "2") (pinfunction "2_2") (pintype "passive"))
    )
    (net (code "29") (name "Net-(C80-Pad1)") (class "Default")
      (node (ref "C80") (pin "1") (pinfunction "1_1") (pintype "passive"))
      (node (ref "R46") (pin "1") (pinfunction "1_1") (pintype "passive"))
      (node (ref "R48") (pin "2") (pinfunction "2_2") (pintype "passive"))
    )
    (net (code "30") (name "Net-(C84-Pad1)") (class "Default")
      (node (ref "C84") (pin "1") (pinfunction "1_1") (pintype "passive"))
      (node (ref "R50") (pin "1") (pinfunction "1_1") (pintype "passive"))
      (node (ref "R51") (pin "2") (pinfunction "2_2") (pintype "passive"))
    )
    (net (code "31") (name "Net-(C90-Pad1)") (class "Default")
      (node (ref "C90") (pin "1") (pinfunction "1_1") (pintype "passive"))
      (node (ref "R52") (pin "1") (pinfunction "1_1") (pintype "passive"))
      (node (ref "R53") (pin "2") (pinfunction "2_2") (pintype "passive"))
    )
    (net (code "32") (name "Net-(C94-Pad1)") (class "Default")
      (node (ref "C94") (pin "1") (pinfunction "1_1") (pintype "passive"))
      (node (ref "R54") (pin "1") (pinfunction "1_1") (pintype "passive"))
      (node (ref "R55") (pin "2") (pinfunction "2_2") (pintype "passive"))
    )
    (net (code "33") (name "Net-(D8-Pad2)") (class "Default")
      (node (ref "D8") (pin "2") (pinfunction "2_2") (pintype "passive"))
      (node (ref "R49") (pin "2") (pinfunction "2_2") (pintype "passive"))
    )
    (net (code "34") (name "Net-(Q3-B)") (class "Default")
      (node (ref "Q3") (pin "1") (pinfunction "B_1") (pintype "passive"))
      (node (ref "R47") (pin "2") (pinfunction "2_2") (pintype "passive"))
    )
    (net (code "35") (name "Net-(U7A-+)") (class "Default")
      (node (ref "C46") (pin "2") (pinfunction "2_2") (pintype "passive"))
      (node (ref "R35") (pin "2") (pinfunction "2_2") (pintype "passive"))
      (node (ref "U7") (pin "3") (pinfunction "+_3") (pintype "passive"))
    )
    (net (code "36") (name "Net-(U7A--)") (class "Default")
      (node (ref "R38") (pin "2") (pinfunction "2_2") (pintype "passive"))
      (node (ref "R39") (pin "1") (pinfunction "1_1") (pintype "passive"))
      (node (ref "U7") (pin "2") (pinfunction "-_2") (pintype "passive"))
    )
    (net (code "37") (name "Net-(U7B-+)") (class "Default")
      (node (ref "C44") (pin "2") (pinfunction "2_2") (pintype "passive"))
      (node (ref "R34") (pin "2") (pinfunction "2_2") (pintype "passive"))
      (node (ref "U7") (pin "5") (pinfunction "+_5") (pintype "passive"))
    )
    (net (code "38") (name "Net-(U7B--)") (class "Default")
      (node (ref "R36") (pin "2") (pinfunction "2_2") (pintype "passive"))
      (node (ref "R37") (pin "1") (pinfunction "1_1") (pintype "passive"))
      (node (ref "U7") (pin "6") (pinfunction "-_6") (pintype "passive"))
    )
    (net (code "39") (name "Net-(U9-DOUT)") (class "Default")
      (node (ref "R44") (pin "2") (pinfunction "2_2") (pintype "passive"))
      (node (ref "U9") (pin "9") (pinfunction "DOUT_9") (pintype "passive"))
    )
    (net (code "40") (name "Net-(U9-VINL)") (class "Default")
      (node (ref "C78") (pin "1") (pinfunction "1_1") (pintype "passive"))
      (node (ref "R42") (pin "1") (pinfunction "1_1") (pintype "passive"))
      (node (ref "U9") (pin "13") (pinfunction "VINL_13") (pintype "passive"))
    )
    (net (code "41") (name "Net-(U9-VINR)") (class "Default")
      (node (ref "C70") (pin "1") (pinfunction "1_1") (pintype "passive"))
      (node (ref "R40") (pin "1") (pinfunction "1_1") (pintype "passive"))
      (node (ref "U9") (pin "14") (pinfunction "VINR_14") (pintype "passive"))
    )
    (net (code "42") (name "Net-(U9-VREF)") (class "Default")
      (node (ref "C72") (pin "2") (pinfunction "2_2") (pintype "passive"))
      (node (ref "C73") (pin "2") (pinfunction "2_2") (pintype "passive"))
      (node (ref "U9") (pin "1") (pinfunction "VREF_1") (pintype "passive"))
    )
    (net (code "43") (name "Net-(U10-DOUT)") (class "Default")
      (node (ref "R45") (pin "2") (pinfunction "2_2") (pintype "passive"))
      (node (ref "U10") (pin "9") (pinfunction "DOUT_9") (pintype "passive"))
    )
    (net (code "44") (name "Net-(U10-VINL)") (class "Default")
      (node (ref "C79") (pin "1") (pinfunction "1_1") (pintype "passive"))
      (node (ref "R43") (pin "1") (pinfunction "1_1") (pintype "passive"))
      (node (ref "U10") (pin "13") (pinfunction "VINL_13") (pintype "passive"))
    )
    (net (code "45") (name "Net-(U10-VINR)") (class "Default")
      (node (ref "C71") (pin "1") (pinfunction "1_1") (pintype "passive"))
      (node (ref "R41") (pin "1") (pinfunction "1_1") (pintype "passive"))
      (node (ref "U10") (pin "14") (pinfunction "VINR_14") (pintype "passive"))
    )
    (net (code "46") (name "Net-(U10-VREF)") (class "Default")
      (node (ref "C74") (pin "2") (pinfunction "2_2") (pintype "passive"))
      (node (ref "C75") (pin "2") (pinfunction "2_2") (pintype "passive"))
      (node (ref "U10") (pin "1") (pinfunction "VREF_1") (pintype "passive"))
    )
    (net (code "47") (name "Net-(U11-AOUTL)") (class "Default")
      (node (ref "C84") (pin "2") (pinfunction "2_2") (pintype "passive"))
      (node (ref "U11") (pin "7") (pinfunction "AOUTL_7") (pintype "passive"))
    )
    (net (code "48") (name "Net-(U11-AOUTR)") (class "Default")
      (node (ref "C80") (pin "2") (pinfunction "2_2") (pintype "passive"))
      (node (ref "U11") (pin "10") (pinfunction "AOUTR_10") (pintype "passive"))
    )
    (net (code "49") (name "Net-(U11-FILT+)") (class "Default")
      (node (ref "C88") (pin "2") (pinfunction "2_2") (pintype "passive"))
      (node (ref "C89") (pin "2") (pinfunction "2_2") (pintype "passive"))
      (node (ref "U11") (pin "6") (pinfunction "FILT+_6") (pintype "passive"))
    )
    (net (code "50") (name "Net-(U11-VQ)") (class "Default")
      (node (ref "C86") (pin "2") (pinfunction "2_2") (pintype "passive"))
      (node (ref "C87") (pin "2") (pinfunction "2_2") (pintype "passive"))
      (node (ref "U11") (pin "5") (pinfunction "VQ_5") (pintype "passive"))
    )
    (net (code "51") (name "Net-(U12-AOUTL)") (class "Default")
      (node (ref "C94") (pin "2") (pinfunction "2_2") (pintype "passive"))
      (node (ref "U12") (pin "7") (pinfunction "AOUTL_7") (pintype "passive"))
    )
    (net (code "52") (name "Net-(U12-AOUTR)") (class "Default")
      (node (ref "C90") (pin "2") (pinfunction "2_2") (pintype "passive"))
      (node (ref "U12") (pin "10") (pinfunction "AOUTR_10") (pintype "passive"))
    )
    (net (code "53") (name "Net-(U12-FILT+)") (class "Default")
      (node (ref "C98") (pin "2") (pinfunction "2_2") (pintype "passive"))
      (node (ref "C99") (pin "2") (pinfunction "2_2") (pintype "passive"))
      (node (ref "U12") (pin "6") (pinfunction "FILT+_6") (pintype "passive"))
    )
    (net (code "54") (name "Net-(U12-VQ)") (class "Default")
      (node (ref "C96") (pin "2") (pinfunction "2_2") (pintype "passive"))
      (node (ref "C97") (pin "2") (pinfunction "2_2") (pintype "passive"))
      (node (ref "U12") (pin "5") (pinfunction "VQ_5") (pintype "passive"))
    )
    (net (code "55") (name "OUT_MIC1") (class "Default")
      (node (ref "C63") (pin "1") (pinfunction "1_1") (pintype "passive"))
      (node (ref "R39") (pin "2") (pinfunction "2_2") (pintype "passive"))
      (node (ref "TP22") (pin "1") (pinfunction "1_1") (pintype "passive"))
      (node (ref "U7") (pin "1") (pinfunction "out_1") (pintype "passive"))
    )
    (net (code "56") (name "OUT_MIC2") (class "Default")
      (node (ref "C77") (pin "1") (pinfunction "1_1") (pintype "passive"))
      (node (ref "R37") (pin "2") (pinfunction "2_2") (pintype "passive"))
      (node (ref "TP24") (pin "1") (pinfunction "1_1") (pintype "passive"))
      (node (ref "U7") (pin "7") (pinfunction "out_7") (pintype "passive"))
    )
    (net (code "57") (name "SCLK_PSRAM64H") (class "Default")
      (node (ref "U8") (pin "6") (pinfunction "SCLK_6") (pintype "passive"))
    )
    (net (code "58") (name "SDIN-1") (class "Default")
      (node (ref "U12") (pin "1") (pinfunction "SDIN_1") (pintype "passive"))
    )
    (net (code "59") (name "SDIN-2") (class "Default")
      (node (ref "U11") (pin "1") (pinfunction "SDIN_1") (pintype "passive"))
    )
    (net (code "60") (name "SIO0_PSRAM64H") (class "Default")
      (node (ref "U8") (pin "5") (pinfunction "SI_5") (pintype "passive"))
    )
    (net (code "61") (name "SIO1_PSRAM64H") (class "Default")
      (node (ref "U8") (pin "2") (pinfunction "SO_2") (pintype "passive"))
    )
    (net (code "62") (name "SIO2_PSRAM64H") (class "Default")
      (node (ref "U8") (pin "3") (pinfunction "SIO[2]_3") (pintype "passive"))
    )
    (net (code "63") (name "SIO3_PSRAM64H") (class "Default")
      (node (ref "U8") (pin "7") (pinfunction "SIO[3]_7") (pintype "passive"))
    )
    (net (code "64") (name "VINL-P1") (class "Default")
      (node (ref "C76") (pin "1") (pinfunction "1_1") (pintype "passive"))
      (node (ref "TP23") (pin "1") (pinfunction "1_1") (pintype "passive"))
    )
    (net (code "65") (name "VINR-P1") (class "Default")
      (node (ref "C60") (pin "1") (pinfunction "1_1") (pintype "passive"))
      (node (ref "TP21") (pin "1") (pinfunction "1_1") (pintype "passive"))
    )
    (net (code "66") (name "WS-1") (class "Default")
      (node (ref "U12") (pin "3") (pinfunction "LRCK_3") (pintype "passive"))
      (node (ref "U9") (pin "7") (pinfunction "LRCK_7") (pintype "passive"))
    )
    (net (code "67") (name "WS-2") (class "Default")
      (node (ref "U10") (pin "7") (pinfunction "LRCK_7") (pintype "passive"))
      (node (ref "U11") (pin "3") (pinfunction "LRCK_3") (pintype "passive"))
    )
  )
)
